# Escorna_CPU_1_20.net
KiCad netlist of a schematic drawn in EAGLE
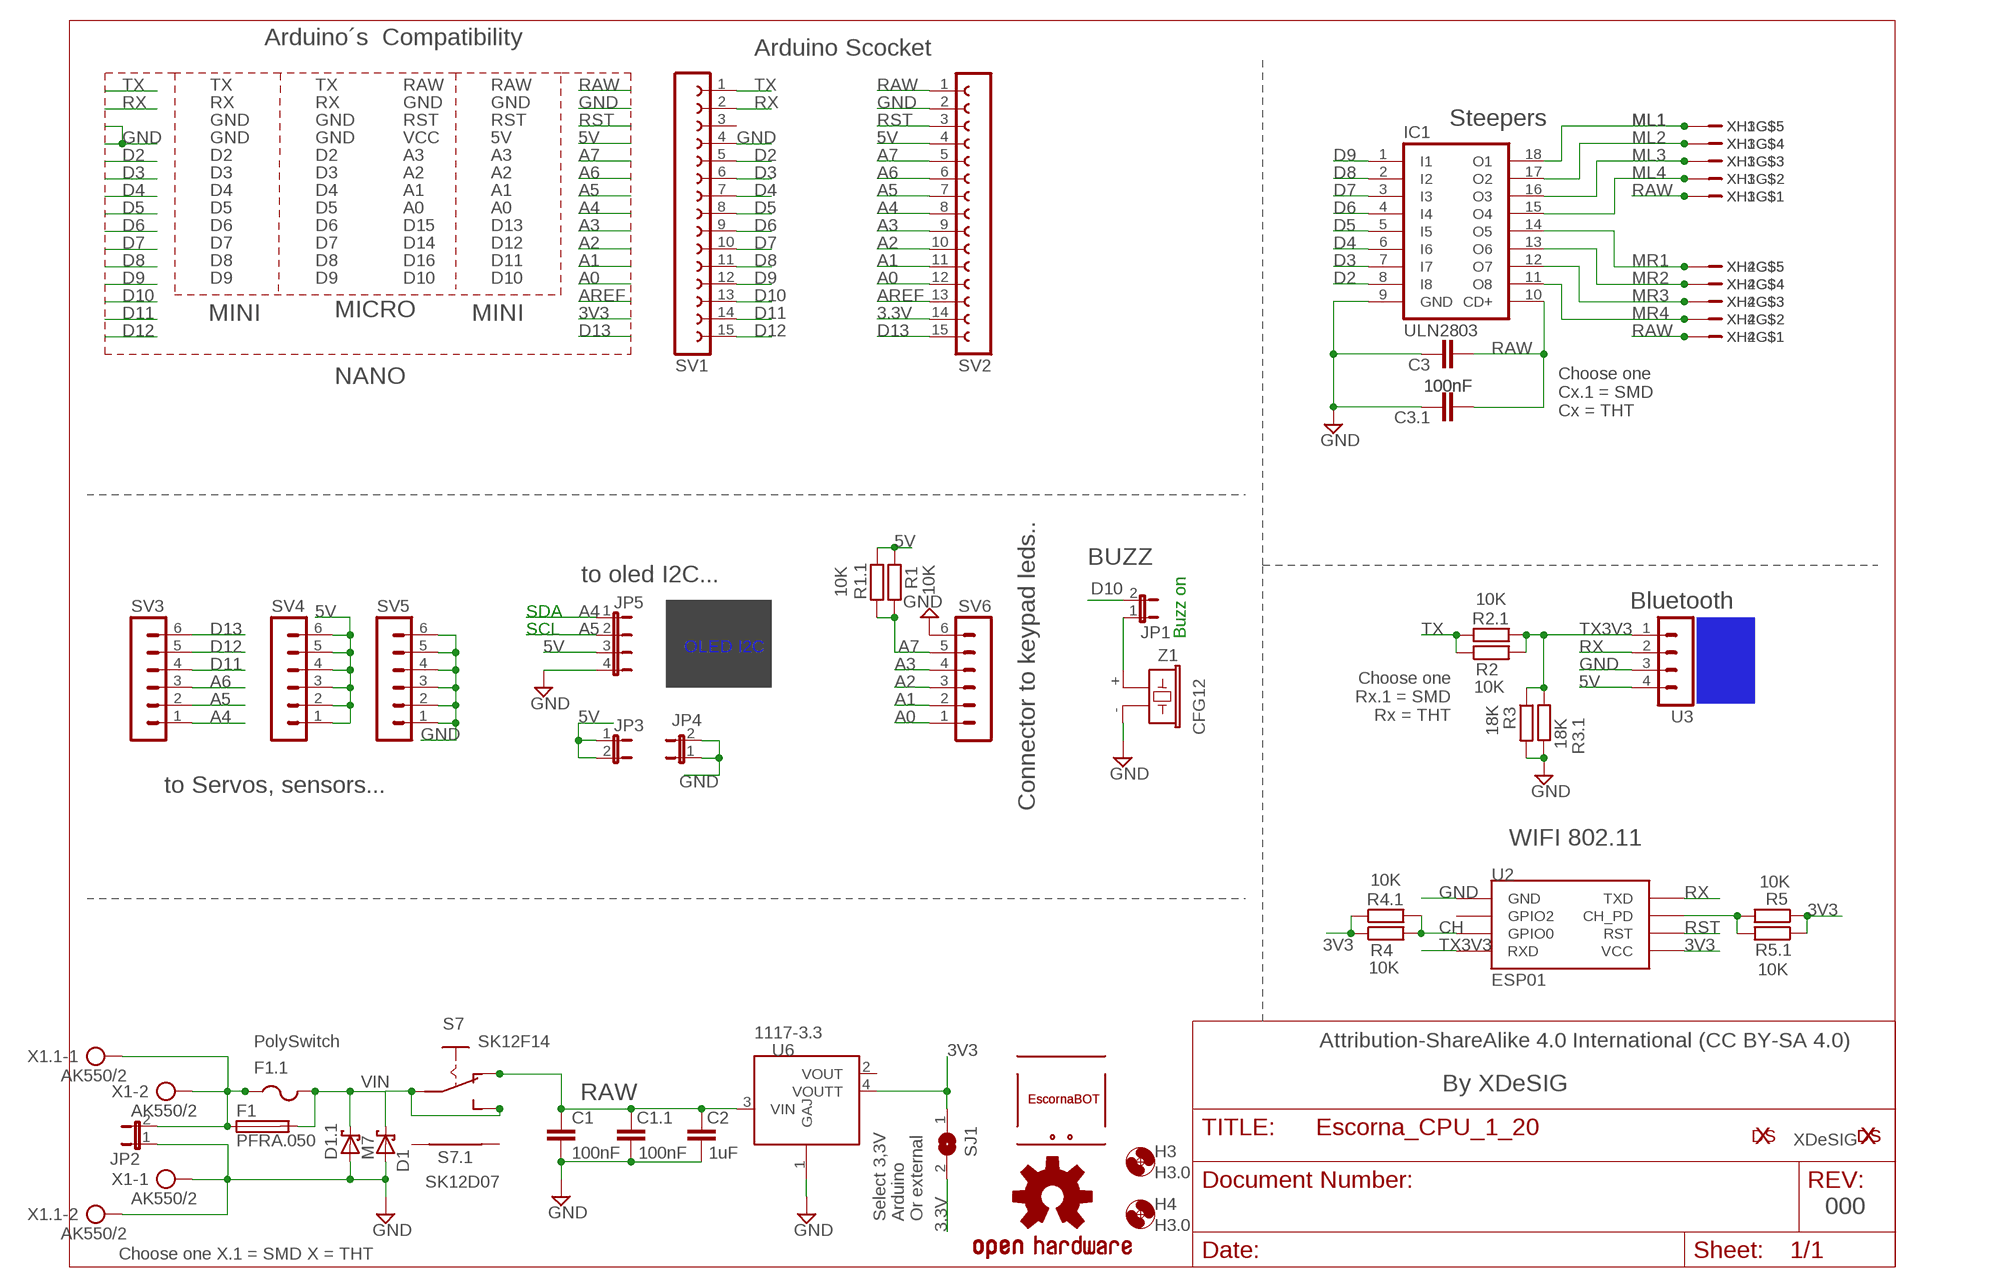
[diagram p0: schematic, sheet 1]

(export (version "E")
  (design (tool "Eeschema 10.0.6"))
  (components
    (comp (ref "C1")
      (value "100nF")
      (footprint "eagle-import:C025-025X050")
      (libsource (lib "eagle-import") (part "C-EU025-025X050"))
    )
    (comp (ref "C1.1")
      (value "100nF")
      (footprint "eagle-import:C0603K")
      (libsource (lib "eagle-import") (part "C-EUC0603K"))
    )
    (comp (ref "C2")
      (value "1uF")
      (footprint "eagle-import:C1206K")
      (libsource (lib "eagle-import") (part "C-EUC1206K"))
    )
    (comp (ref "C3")
      (value "100nF")
      (footprint "eagle-import:C025-025X050")
      (libsource (lib "eagle-import") (part "C-EU025-025X050"))
    )
    (comp (ref "C3.1")
      (value "100nF")
      (footprint "eagle-import:C0603K")
      (libsource (lib "eagle-import") (part "C-EUC0603K"))
    )
    (comp (ref "D1")
      (value "1N5817")
      (footprint "eagle-import:DO41-10")
      (libsource (lib "eagle-import") (part "P4KEXX"))
    )
    (comp (ref "D1.1")
      (value "M7")
      (footprint "eagle-import:SMA-DO214AC")
      (libsource (lib "eagle-import") (part "SCHOTTKY-DIODE"))
    )
    (comp (ref "ESC1")
      (value "ESCORNABOT")
      (footprint "eagle-import:ESCORNA_PEQUE")
      (libsource (lib "eagle-import") (part "ESCORNABOT"))
    )
    (comp (ref "ESC2")
      (value "ESCORNABOT")
      (footprint "eagle-import:ESCORNA_PEQUE")
      (libsource (lib "eagle-import") (part "ESCORNABOT"))
    )
    (comp (ref "F1")
      (value "PFRA.050")
      (footprint "eagle-import:TE5")
      (libsource (lib "eagle-import") (part "FUSETE5"))
    )
    (comp (ref "F1.1")
      (value "PolySwitch")
      (footprint "eagle-import:R1206")
      (libsource (lib "eagle-import") (part "PTCFUSE-1206"))
    )
    (comp (ref "H3")
      (value "H3.0")
      (footprint "eagle-import:3,0")
      (libsource (lib "eagle-import") (part "MOUNT-HOLE3.0"))
    )
    (comp (ref "H4")
      (value "H3.0")
      (footprint "eagle-import:3,0")
      (libsource (lib "eagle-import") (part "MOUNT-HOLE3.0"))
    )
    (comp (ref "IC1")
      (value "ULN2803")
      (footprint "eagle-import:DIL18")
      (libsource (lib "eagle-import") (part "ULN2803A"))
    )
    (comp (ref "JP1")
      (value "JP1E")
      (footprint "eagle-import:1X02")
      (libsource (lib "eagle-import") (part "JP1E"))
    )
    (comp (ref "JP2")
      (value "JP1E")
      (footprint "eagle-import:1X02")
      (libsource (lib "eagle-import") (part "JP1E"))
    )
    (comp (ref "JP3")
      (value "JP1E")
      (footprint "eagle-import:JP1")
      (libsource (lib "eagle-import") (part "jumper_JP1E"))
    )
    (comp (ref "JP4")
      (value "JP1E")
      (footprint "eagle-import:JP1")
      (libsource (lib "eagle-import") (part "jumper_JP1E"))
    )
    (comp (ref "JP5")
      (value "JP4E")
      (footprint "eagle-import:JP4")
      (libsource (lib "eagle-import") (part "JP4E"))
    )
    (comp (ref "LOGO2")
      (value "OSHW-LOGOS")
      (footprint "eagle-import:OSHW-LOGO-S")
      (libsource (lib "eagle-import") (part "OSHW-LOGOS"))
    )
    (comp (ref "R1")
      (value "10K")
      (footprint "eagle-import:0204_7")
      (libsource (lib "eagle-import") (part "R-EU_0204/7"))
    )
    (comp (ref "R1.1")
      (value "10K")
      (footprint "eagle-import:R0603")
      (libsource (lib "eagle-import") (part "R-EU_R0603"))
    )
    (comp (ref "R2")
      (value "10K")
      (footprint "eagle-import:0204_7")
      (libsource (lib "eagle-import") (part "R-EU_0204/7"))
    )
    (comp (ref "R2.1")
      (value "10K")
      (footprint "eagle-import:R0603")
      (libsource (lib "eagle-import") (part "R-EU_R0603"))
    )
    (comp (ref "R3")
      (value "18K")
      (footprint "eagle-import:0204_7")
      (libsource (lib "eagle-import") (part "R-EU_0204/7"))
    )
    (comp (ref "R3.1")
      (value "18K")
      (footprint "eagle-import:R0603")
      (libsource (lib "eagle-import") (part "R-EU_R0603"))
    )
    (comp (ref "R4")
      (value "10K")
      (footprint "eagle-import:0204_7")
      (libsource (lib "eagle-import") (part "R-EU_0204/7"))
    )
    (comp (ref "R4.1")
      (value "10K")
      (footprint "eagle-import:R0603")
      (libsource (lib "eagle-import") (part "R-EU_R0603"))
    )
    (comp (ref "R5")
      (value "10K")
      (footprint "eagle-import:0204_7")
      (libsource (lib "eagle-import") (part "R-EU_0204/7"))
    )
    (comp (ref "R5.1")
      (value "10K")
      (footprint "eagle-import:R0603")
      (libsource (lib "eagle-import") (part "R-EU_R0603"))
    )
    (comp (ref "S7")
      (value "SK12F14")
      (footprint "eagle-import:ESCORNA_SK-12F14-G")
      (libsource (lib "eagle-import") (part "ESCORNA_SK12F14F"))
    )
    (comp (ref "S7.1")
      (value "SK12D07")
      (footprint "eagle-import:ESCORNA_SK-12D07")
      (libsource (lib "eagle-import") (part "ESCORNA_SK12F14D"))
    )
    (comp (ref "SJ1") (value "SJ") (footprint "eagle-import:SJ") (libsource (lib "eagle-import") (part "SJ")))
    (comp (ref "SV1")
      (value "1x15 SOCKET STRIP")
      (footprint "eagle-import:CON-LSTA_FE15")
      (libsource (lib "eagle-import") (part "CON-LSTA_FE15-1"))
    )
    (comp (ref "SV2")
      (value "1x15 SOCKET STRIP")
      (footprint "eagle-import:CON-LSTA_FE15")
      (libsource (lib "eagle-import") (part "CON-LSTA_FE15-1"))
    )
    (comp (ref "SV3")
      (value "MA06-1")
      (footprint "eagle-import:MA06-1")
      (libsource (lib "eagle-import") (part "MA06-1"))
    )
    (comp (ref "SV4")
      (value "MA06-1")
      (footprint "eagle-import:MA06-1")
      (libsource (lib "eagle-import") (part "MA06-1"))
    )
    (comp (ref "SV5")
      (value "MA06-1")
      (footprint "eagle-import:MA06-1")
      (libsource (lib "eagle-import") (part "MA06-1"))
    )
    (comp (ref "SV6")
      (value "MA06-1")
      (footprint "eagle-import:MA06-1")
      (libsource (lib "eagle-import") (part "MA06-1"))
    )
    (comp (ref "U$1")
      (value "XDESIG_XDESIG21")
      (footprint "eagle-import:XDESIG_XDESIG")
      (libsource (lib "eagle-import") (part "XDESIG_XDESIG21"))
    )
    (comp (ref "U$13")
      (value "XDESIG_XDESIG21")
      (footprint "eagle-import:XDESIG_XDESIG")
      (libsource (lib "eagle-import") (part "XDESIG_XDESIG21"))
    )
    (comp (ref "U2")
      (value "ESP01")
      (footprint "eagle-import:ESP01")
      (libsource (lib "eagle-import") (part "ESP01"))
    )
    (comp (ref "U3")
      (value "MA04-1")
      (footprint "eagle-import:MA04-1")
      (libsource (lib "eagle-import") (part "MA04-1"))
    )
    (comp (ref "U6")
      (value "1117-3.3")
      (footprint "eagle-import:SOT223")
      (libsource (lib "eagle-import") (part "ASM1117-3.3"))
    )
    (comp (ref "X1")
      (value "AK550/2")
      (footprint "eagle-import:AK550_2")
      (libsource (lib "eagle-import") (part "AK550/2"))
    )
    (comp (ref "X1.1")
      (value "AK550/2")
      (footprint "eagle-import:AK550_2")
      (fields (field (name "OC_FARNELL") "unknown") (field (name "OC_NEWARK") "unknown"))
      (libsource (lib "eagle-import") (part "AK550/2"))
    )
    (comp (ref "XDS1")
      (value "XDESIG")
      (footprint "eagle-import:XDESIG_CU_2")
      (libsource (lib "eagle-import") (part "XDESIG"))
    )
    (comp (ref "XH1")
      (value "B5B-XH-A")
      (footprint "eagle-import:B5B-XH-A")
      (libsource (lib "eagle-import") (part "B5B-XH-A"))
    )
    (comp (ref "XH2")
      (value "B5B-XH-A")
      (footprint "eagle-import:B5B-XH-A")
      (libsource (lib "eagle-import") (part "B5B-XH-A"))
    )
    (comp (ref "XH3")
      (value "B5B-XH-A")
      (footprint "eagle-import:B5B-XH-A")
      (libsource (lib "eagle-import") (part "B5B-XH-A"))
    )
    (comp (ref "XH4")
      (value "B5B-XH-A")
      (footprint "eagle-import:B5B-XH-A")
      (libsource (lib "eagle-import") (part "B5B-XH-A"))
    )
    (comp (ref "Z1")
      (value "CFG12")
      (footprint "eagle-import:F_CM12P")
      (libsource (lib "eagle-import") (part "F/CM12P"))
    )
  )
  (nets
    (net (code "1") (name "/3.3V") (class "Default")
      (node (ref "SJ1") (pin "2") (pinfunction "2_2") (pintype "passive"))
      (node (ref "SV2") (pin "14") (pinfunction "14_14") (pintype "passive"))
    )
    (net (code "2") (name "/3V3") (class "Default")
      (node (ref "R4") (pin "1") (pinfunction "1_1") (pintype "passive"))
      (node (ref "R4.1") (pin "1") (pinfunction "1_1") (pintype "passive"))
      (node (ref "R5") (pin "1") (pinfunction "1_1") (pintype "passive"))
      (node (ref "R5.1") (pin "1") (pinfunction "1_1") (pintype "passive"))
      (node (ref "SJ1") (pin "1") (pinfunction "1_1") (pintype "passive"))
      (node (ref "U2") (pin "VCC") (pinfunction "VCC_VCC") (pintype "bidirectional"))
      (node (ref "U6") (pin "4") (pinfunction "VOUTT_4") (pintype "bidirectional"))
    )
    (net (code "3") (name "/5V") (class "Default")
      (node (ref "JP3") (pin "1") (pinfunction "1_1") (pintype "passive"))
      (node (ref "JP3") (pin "2") (pinfunction "2_2") (pintype "passive"))
      (node (ref "JP5") (pin "3") (pinfunction "3_3") (pintype "passive"))
      (node (ref "R1") (pin "1") (pinfunction "1_1") (pintype "passive"))
      (node (ref "R1.1") (pin "1") (pinfunction "1_1") (pintype "passive"))
      (node (ref "SV2") (pin "4") (pinfunction "4_4") (pintype "passive"))
      (node (ref "SV4") (pin "1") (pinfunction "1_1") (pintype "passive"))
      (node (ref "SV4") (pin "2") (pinfunction "2_2") (pintype "passive"))
      (node (ref "SV4") (pin "3") (pinfunction "3_3") (pintype "passive"))
      (node (ref "SV4") (pin "4") (pinfunction "4_4") (pintype "passive"))
      (node (ref "SV4") (pin "5") (pinfunction "5_5") (pintype "passive"))
      (node (ref "SV4") (pin "6") (pinfunction "6_6") (pintype "passive"))
      (node (ref "U3") (pin "4") (pinfunction "4_4") (pintype "passive"))
    )
    (net (code "4") (name "/A0") (class "Default")
      (node (ref "SV2") (pin "12") (pinfunction "12_12") (pintype "passive"))
      (node (ref "SV6") (pin "1") (pinfunction "1_1") (pintype "passive"))
    )
    (net (code "5") (name "/A1") (class "Default")
      (node (ref "SV2") (pin "11") (pinfunction "11_11") (pintype "passive"))
      (node (ref "SV6") (pin "2") (pinfunction "2_2") (pintype "passive"))
    )
    (net (code "6") (name "/A2") (class "Default")
      (node (ref "SV2") (pin "10") (pinfunction "10_10") (pintype "passive"))
      (node (ref "SV6") (pin "3") (pinfunction "3_3") (pintype "passive"))
    )
    (net (code "7") (name "/A3") (class "Default")
      (node (ref "SV2") (pin "9") (pinfunction "9_9") (pintype "passive"))
      (node (ref "SV6") (pin "4") (pinfunction "4_4") (pintype "passive"))
    )
    (net (code "8") (name "/A4") (class "Default")
      (node (ref "JP5") (pin "1") (pinfunction "1_1") (pintype "passive"))
      (node (ref "SV2") (pin "8") (pinfunction "8_8") (pintype "passive"))
      (node (ref "SV3") (pin "1") (pinfunction "1_1") (pintype "passive"))
    )
    (net (code "9") (name "/A5") (class "Default")
      (node (ref "JP5") (pin "2") (pinfunction "2_2") (pintype "passive"))
      (node (ref "SV2") (pin "7") (pinfunction "7_7") (pintype "passive"))
      (node (ref "SV3") (pin "2") (pinfunction "2_2") (pintype "passive"))
    )
    (net (code "10") (name "/A6") (class "Default")
      (node (ref "SV2") (pin "6") (pinfunction "6_6") (pintype "passive"))
      (node (ref "SV3") (pin "3") (pinfunction "3_3") (pintype "passive"))
    )
    (net (code "11") (name "/A7") (class "Default")
      (node (ref "R1") (pin "2") (pinfunction "2_2") (pintype "passive"))
      (node (ref "R1.1") (pin "2") (pinfunction "2_2") (pintype "passive"))
      (node (ref "SV2") (pin "5") (pinfunction "5_5") (pintype "passive"))
      (node (ref "SV6") (pin "5") (pinfunction "5_5") (pintype "passive"))
    )
    (net (code "12") (name "/AREF") (class "Default")
      (node (ref "SV2") (pin "13") (pinfunction "13_13") (pintype "passive"))
    )
    (net (code "13") (name "/CH") (class "Default")
      (node (ref "R4") (pin "2") (pinfunction "2_2") (pintype "passive"))
      (node (ref "R4.1") (pin "2") (pinfunction "2_2") (pintype "passive"))
      (node (ref "U2") (pin "GPIO0") (pinfunction "GPIO0_GPIO0") (pintype "bidirectional"))
    )
    (net (code "14") (name "/D2") (class "Default")
      (node (ref "IC1") (pin "8") (pinfunction "I8_8") (pintype "input"))
      (node (ref "SV1") (pin "5") (pinfunction "5_5") (pintype "passive"))
    )
    (net (code "15") (name "/D3") (class "Default")
      (node (ref "IC1") (pin "7") (pinfunction "I7_7") (pintype "input"))
      (node (ref "SV1") (pin "6") (pinfunction "6_6") (pintype "passive"))
    )
    (net (code "16") (name "/D4") (class "Default")
      (node (ref "IC1") (pin "6") (pinfunction "I6_6") (pintype "input"))
      (node (ref "SV1") (pin "7") (pinfunction "7_7") (pintype "passive"))
    )
    (net (code "17") (name "/D5") (class "Default")
      (node (ref "IC1") (pin "5") (pinfunction "I5_5") (pintype "input"))
      (node (ref "SV1") (pin "8") (pinfunction "8_8") (pintype "passive"))
    )
    (net (code "18") (name "/D6") (class "Default")
      (node (ref "IC1") (pin "4") (pinfunction "I4_4") (pintype "input"))
      (node (ref "SV1") (pin "9") (pinfunction "9_9") (pintype "passive"))
    )
    (net (code "19") (name "/D7") (class "Default")
      (node (ref "IC1") (pin "3") (pinfunction "I3_3") (pintype "input"))
      (node (ref "SV1") (pin "10") (pinfunction "10_10") (pintype "passive"))
    )
    (net (code "20") (name "/D8") (class "Default")
      (node (ref "IC1") (pin "2") (pinfunction "I2_2") (pintype "input"))
      (node (ref "SV1") (pin "11") (pinfunction "11_11") (pintype "passive"))
    )
    (net (code "21") (name "/D9") (class "Default")
      (node (ref "IC1") (pin "1") (pinfunction "I1_1") (pintype "input"))
      (node (ref "SV1") (pin "12") (pinfunction "12_12") (pintype "passive"))
    )
    (net (code "22") (name "/D10") (class "Default")
      (node (ref "JP1") (pin "2") (pinfunction "2_2") (pintype "passive"))
      (node (ref "SV1") (pin "13") (pinfunction "13_13") (pintype "passive"))
    )
    (net (code "23") (name "/D11") (class "Default")
      (node (ref "SV1") (pin "14") (pinfunction "14_14") (pintype "passive"))
      (node (ref "SV3") (pin "4") (pinfunction "4_4") (pintype "passive"))
    )
    (net (code "24") (name "/D12") (class "Default")
      (node (ref "SV1") (pin "15") (pinfunction "15_15") (pintype "passive"))
      (node (ref "SV3") (pin "5") (pinfunction "5_5") (pintype "passive"))
    )
    (net (code "25") (name "/D13") (class "Default")
      (node (ref "SV2") (pin "15") (pinfunction "15_15") (pintype "passive"))
      (node (ref "SV3") (pin "6") (pinfunction "6_6") (pintype "passive"))
    )
    (net (code "26") (name "/ML1") (class "Default")
      (node (ref "IC1") (pin "18") (pinfunction "O1_18") (pintype "open_collector"))
      (node (ref "XH1") (pin "P$5") (pinfunction "1_P$5") (pintype "passive"))
      (node (ref "XH3") (pin "P$5") (pinfunction "1_P$5") (pintype "passive"))
    )
    (net (code "27") (name "/ML2") (class "Default")
      (node (ref "IC1") (pin "17") (pinfunction "O2_17") (pintype "open_collector"))
      (node (ref "XH1") (pin "P$4") (pinfunction "1_P$4") (pintype "passive"))
      (node (ref "XH3") (pin "P$4") (pinfunction "1_P$4") (pintype "passive"))
    )
    (net (code "28") (name "/ML3") (class "Default")
      (node (ref "IC1") (pin "16") (pinfunction "O3_16") (pintype "open_collector"))
      (node (ref "XH1") (pin "P$3") (pinfunction "1_P$3") (pintype "passive"))
      (node (ref "XH3") (pin "P$3") (pinfunction "1_P$3") (pintype "passive"))
    )
    (net (code "29") (name "/ML4") (class "Default")
      (node (ref "IC1") (pin "15") (pinfunction "O4_15") (pintype "open_collector"))
      (node (ref "XH1") (pin "P$2") (pinfunction "1_P$2") (pintype "passive"))
      (node (ref "XH3") (pin "P$2") (pinfunction "1_P$2") (pintype "passive"))
    )
    (net (code "30") (name "/MR1") (class "Default")
      (node (ref "IC1") (pin "14") (pinfunction "O5_14") (pintype "open_collector"))
      (node (ref "XH2") (pin "P$5") (pinfunction "1_P$5") (pintype "passive"))
      (node (ref "XH4") (pin "P$5") (pinfunction "1_P$5") (pintype "passive"))
    )
    (net (code "31") (name "/MR2") (class "Default")
      (node (ref "IC1") (pin "13") (pinfunction "O6_13") (pintype "open_collector"))
      (node (ref "XH2") (pin "P$4") (pinfunction "1_P$4") (pintype "passive"))
      (node (ref "XH4") (pin "P$4") (pinfunction "1_P$4") (pintype "passive"))
    )
    (net (code "32") (name "/MR3") (class "Default")
      (node (ref "IC1") (pin "12") (pinfunction "O7_12") (pintype "open_collector"))
      (node (ref "XH2") (pin "P$3") (pinfunction "1_P$3") (pintype "passive"))
      (node (ref "XH4") (pin "P$3") (pinfunction "1_P$3") (pintype "passive"))
    )
    (net (code "33") (name "/MR4") (class "Default")
      (node (ref "IC1") (pin "11") (pinfunction "O8_11") (pintype "open_collector"))
      (node (ref "XH2") (pin "P$2") (pinfunction "1_P$2") (pintype "passive"))
      (node (ref "XH4") (pin "P$2") (pinfunction "1_P$2") (pintype "passive"))
    )
    (net (code "34") (name "/RAW") (class "Default")
      (node (ref "C1") (pin "1") (pinfunction "1_1") (pintype "passive"))
      (node (ref "C1.1") (pin "2") (pinfunction "2_2") (pintype "passive"))
      (node (ref "C2") (pin "2") (pinfunction "2_2") (pintype "passive"))
      (node (ref "C3") (pin "2") (pinfunction "2_2") (pintype "passive"))
      (node (ref "C3.1") (pin "2") (pinfunction "2_2") (pintype "passive"))
      (node (ref "IC1") (pin "10") (pinfunction "CD+_10") (pintype "passive"))
      (node (ref "S7") (pin "P$2") (pinfunction "O_P$2") (pintype "passive"))
      (node (ref "S7.1") (pin "P$2") (pinfunction "O_P$2") (pintype "passive"))
      (node (ref "SV2") (pin "1") (pinfunction "1_1") (pintype "passive"))
      (node (ref "U6") (pin "3") (pinfunction "VIN_3") (pintype "bidirectional"))
      (node (ref "XH1") (pin "P$1") (pinfunction "1_P$1") (pintype "passive"))
      (node (ref "XH2") (pin "P$1") (pinfunction "1_P$1") (pintype "passive"))
      (node (ref "XH3") (pin "P$1") (pinfunction "1_P$1") (pintype "passive"))
      (node (ref "XH4") (pin "P$1") (pinfunction "1_P$1") (pintype "passive"))
    )
    (net (code "35") (name "/RST") (class "Default")
      (node (ref "SV2") (pin "3") (pinfunction "3_3") (pintype "passive"))
      (node (ref "U2") (pin "RST") (pinfunction "RST_RST") (pintype "bidirectional"))
    )
    (net (code "36") (name "/RX") (class "Default")
      (node (ref "SV1") (pin "2") (pinfunction "2_2") (pintype "passive"))
      (node (ref "U2") (pin "TX") (pinfunction "TXD_TX") (pintype "bidirectional"))
      (node (ref "U3") (pin "2") (pinfunction "2_2") (pintype "passive"))
    )
    (net (code "37") (name "/TX") (class "Default")
      (node (ref "R2") (pin "1") (pinfunction "1_1") (pintype "passive"))
      (node (ref "R2.1") (pin "1") (pinfunction "1_1") (pintype "passive"))
      (node (ref "SV1") (pin "1") (pinfunction "1_1") (pintype "passive"))
    )
    (net (code "38") (name "/TX3V3") (class "Default")
      (node (ref "R2") (pin "2") (pinfunction "2_2") (pintype "passive"))
      (node (ref "R2.1") (pin "2") (pinfunction "2_2") (pintype "passive"))
      (node (ref "R3") (pin "1") (pinfunction "1_1") (pintype "passive"))
      (node (ref "R3.1") (pin "2") (pinfunction "2_2") (pintype "passive"))
      (node (ref "U2") (pin "RX") (pinfunction "RXD_RX") (pintype "bidirectional"))
      (node (ref "U3") (pin "1") (pinfunction "1_1") (pintype "passive"))
    )
    (net (code "39") (name "/VIN") (class "Default")
      (node (ref "D1") (pin "C") (pinfunction "C_C") (pintype "passive"))
      (node (ref "D1.1") (pin "K") (pinfunction "C_K") (pintype "passive"))
      (node (ref "F1") (pin "2") (pinfunction "2_2") (pintype "passive"))
      (node (ref "F1.1") (pin "2") (pinfunction "2_2") (pintype "passive"))
      (node (ref "S7") (pin "P$1") (pinfunction "P_P$1") (pintype "passive"))
      (node (ref "S7") (pin "P$3") (pinfunction "S_P$3") (pintype "passive"))
      (node (ref "S7.1") (pin "P$1") (pinfunction "P_P$1") (pintype "passive"))
      (node (ref "S7.1") (pin "P$3") (pinfunction "S_P$3") (pintype "passive"))
    )
    (net (code "40") (name "GND") (class "Default")
      (node (ref "C1") (pin "2") (pinfunction "2_2") (pintype "passive"))
      (node (ref "C1.1") (pin "1") (pinfunction "1_1") (pintype "passive"))
      (node (ref "C2") (pin "1") (pinfunction "1_1") (pintype "passive"))
      (node (ref "C3") (pin "1") (pinfunction "1_1") (pintype "passive"))
      (node (ref "C3.1") (pin "1") (pinfunction "1_1") (pintype "passive"))
      (node (ref "D1") (pin "A") (pinfunction "A_A") (pintype "passive"))
      (node (ref "D1.1") (pin "A") (pinfunction "A_A") (pintype "passive"))
      (node (ref "IC1") (pin "9") (pinfunction "GND_9") (pintype "power_in"))
      (node (ref "JP2") (pin "1") (pinfunction "1_1") (pintype "passive"))
      (node (ref "JP4") (pin "1") (pinfunction "1_1") (pintype "passive"))
      (node (ref "JP4") (pin "2") (pinfunction "2_2") (pintype "passive"))
      (node (ref "JP5") (pin "4") (pinfunction "4_4") (pintype "passive"))
      (node (ref "R3") (pin "2") (pinfunction "2_2") (pintype "passive"))
      (node (ref "R3.1") (pin "1") (pinfunction "1_1") (pintype "passive"))
      (node (ref "SV1") (pin "4") (pinfunction "4_4") (pintype "passive"))
      (node (ref "SV2") (pin "2") (pinfunction "2_2") (pintype "passive"))
      (node (ref "SV5") (pin "1") (pinfunction "1_1") (pintype "passive"))
      (node (ref "SV5") (pin "2") (pinfunction "2_2") (pintype "passive"))
      (node (ref "SV5") (pin "3") (pinfunction "3_3") (pintype "passive"))
      (node (ref "SV5") (pin "4") (pinfunction "4_4") (pintype "passive"))
      (node (ref "SV5") (pin "5") (pinfunction "5_5") (pintype "passive"))
      (node (ref "SV5") (pin "6") (pinfunction "6_6") (pintype "passive"))
      (node (ref "SV6") (pin "6") (pinfunction "6_6") (pintype "passive"))
      (node (ref "U2") (pin "GND") (pinfunction "GND_GND") (pintype "bidirectional"))
      (node (ref "U3") (pin "3") (pinfunction "3_3") (pintype "passive"))
      (node (ref "U6") (pin "1") (pinfunction "GAJ_1") (pintype "bidirectional"))
      (node (ref "X1") (pin "1") (pinfunction "KL_1") (pintype "passive"))
      (node (ref "X1.1") (pin "2") (pinfunction "KL_2") (pintype "passive"))
      (node (ref "Z1") (pin "-") (pinfunction "2_-") (pintype "passive"))
    )
    (net (code "41") (name "Net-(R5-Pad2)") (class "Default")
      (node (ref "R5") (pin "2") (pinfunction "2_2") (pintype "passive"))
      (node (ref "R5.1") (pin "2") (pinfunction "2_2") (pintype "passive"))
      (node (ref "U2") (pin "CH_PD") (pinfunction "CH_PD_CH_PD") (pintype "bidirectional"))
    )
    (net (code "42") (name "Net-(S7-P$1)") (class "Default")
      (node (ref "S7") (pin "P$4") (pinfunction "P$1_P$4") (pintype "passive"))
      (node (ref "S7.1") (pin "P$4") (pinfunction "P$1_P$4") (pintype "passive"))
    )
    (net (code "43") (name "Net-(S7-P$2)") (class "Default")
      (node (ref "S7") (pin "P$5") (pinfunction "P$2_P$5") (pintype "bidirectional"))
      (node (ref "S7.1") (pin "P$5") (pinfunction "P$2_P$5") (pintype "bidirectional"))
    )
    (net (code "44") (name "Net-(X1.1A-KL)") (class "Default")
      (node (ref "F1") (pin "1") (pinfunction "1_1") (pintype "passive"))
      (node (ref "F1.1") (pin "1") (pinfunction "1_1") (pintype "passive"))
      (node (ref "JP2") (pin "2") (pinfunction "2_2") (pintype "passive"))
      (node (ref "X1") (pin "2") (pinfunction "KL_2") (pintype "passive"))
      (node (ref "X1.1") (pin "1") (pinfunction "KL_1") (pintype "passive"))
    )
    (net (code "45") (name "Net-(Z1-1)") (class "Default")
      (node (ref "JP1") (pin "1") (pinfunction "1_1") (pintype "passive"))
      (node (ref "Z1") (pin "+") (pinfunction "1_+") (pintype "passive"))
    )
    (net (code "46") (name "unconnected-(SV1-Pad3)") (class "Default")
      (node (ref "SV1") (pin "3") (pinfunction "3_3") (pintype "passive"))
    )
    (net (code "47") (name "unconnected-(U2-PadGPIO2)") (class "Default")
      (node (ref "U2") (pin "GPIO2") (pinfunction "GPIO2_GPIO2") (pintype "bidirectional"))
    )
    (net (code "48") (name "unconnected-(U6-VOUT-Pad2)") (class "Default")
      (node (ref "U6") (pin "2") (pinfunction "VOUT_2") (pintype "bidirectional"))
    )
  )
)
